# main.net
KiCad netlist of a schematic drawn in Altium Designer
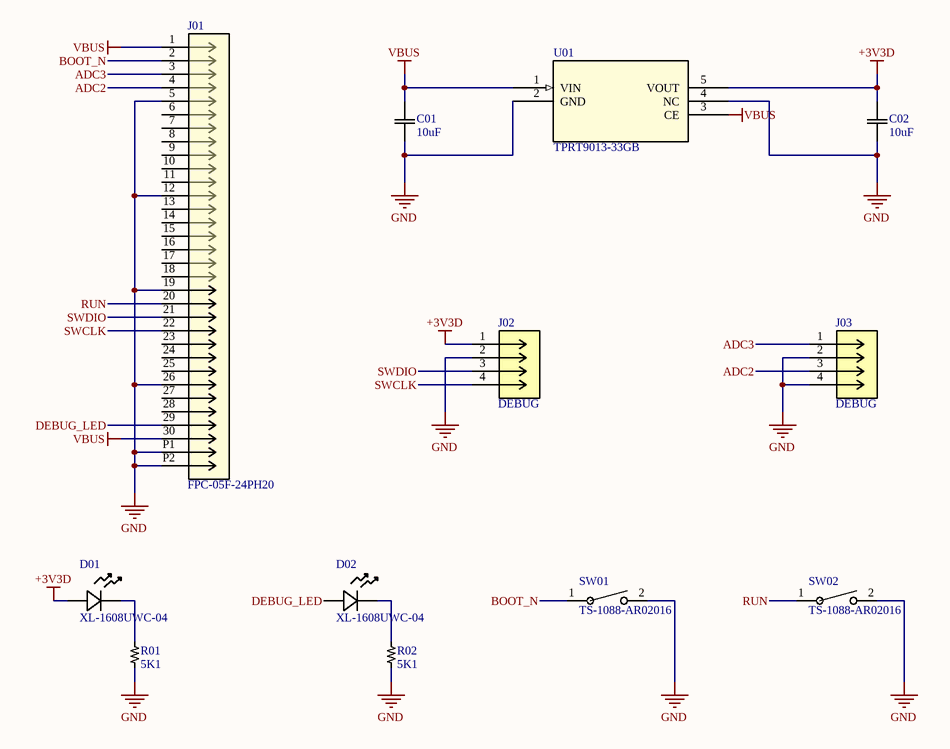
[diagram p0: main.SchDoc]

(export (version "E")
  (design (tool "Eeschema 10.0.6"))
  (components
    (comp (ref "C01")
      (value "10uF")
      (footprint "CAPC10555_55N_KEM")
      (description "SMD Comm X7R, Ceramic, SMD, MLCC, Temperature Stable, 0402")
      (fields
        (field (name "MANUFACTURER_PART_NUMBER") "C0402C104K4RACTU")
        (field (name "COPYRIGHT") "Copyright (C) 2025 Ultra Librarian. All rights reserved.")
      )
      (libsource (lib "SplitHE_Int") (part "C0402"))
    )
    (comp (ref "C02")
      (value "10uF")
      (footprint "CAPC10555_55N_KEM")
      (description "SMD Comm X7R, Ceramic, SMD, MLCC, Temperature Stable, 0402")
      (fields
        (field (name "MANUFACTURER_PART_NUMBER") "C0402C104K4RACTU")
        (field (name "COPYRIGHT") "Copyright (C) 2025 Ultra Librarian. All rights reserved.")
      )
      (libsource (lib "SplitHE_Int") (part "C0402"))
    )
    (comp (ref "D01")
      (value "XL-1608UWC-04")
      (footprint "LED_XL-1608_XLG")
      (description "No Description Available")
      (fields (field (name "COPYRIGHT") "Copyright (C) 2025 Ultra Librarian. All rights reserved."))
      (libsource (lib "SplitHE_Int") (part "XL-1608UWC-04"))
    )
    (comp (ref "D02")
      (value "XL-1608UWC-04")
      (footprint "LED_XL-1608_XLG")
      (description "No Description Available")
      (fields (field (name "COPYRIGHT") "Copyright (C) 2025 Ultra Librarian. All rights reserved."))
      (libsource (lib "SplitHE_Int") (part "XL-1608UWC-04"))
    )
    (comp (ref "J01")
      (value "FPC-05F-24PH20")
      (footprint "FPC-05F-30PH20")
      (description "32 Pin 0.5 Pitch FPC connector")
      (libsource (lib "SplitHE_COPY_073026") (part "FPC-05F-32PH20"))
    )
    (comp (ref "J02")
      (value "DEBUG")
      (footprint "SW_Debugger_4P")
      (description "Back up plan for debugging")
      (libsource (lib "SplitHE_Int") (part "DEBUG_4"))
    )
    (comp (ref "J03")
      (value "DEBUG")
      (footprint "SW_Debugger_4P")
      (description "Back up plan for debugging")
      (libsource (lib "SplitHE_Int") (part "DEBUG_4"))
    )
    (comp (ref "R01")
      (value "5K1")
      (footprint "RES0402_CPF_TYCO_TYC")
      (description "CPF 0402 RL")
      (fields
        (field (name "MANUFACTURER_PART_NUMBER") "CPF0402B33RE1")
        (field (name "COPYRIGHT") "Copyright (C) 2025 Ultra Librarian. All rights reserved.")
      )
      (libsource (lib "SplitHE_Int") (part "R0402"))
    )
    (comp (ref "R02")
      (value "5K1")
      (footprint "RES0402_CPF_TYCO_TYC")
      (description "CPF 0402 RL")
      (fields
        (field (name "MANUFACTURER_PART_NUMBER") "CPF0402B33RE1")
        (field (name "COPYRIGHT") "Copyright (C) 2025 Ultra Librarian. All rights reserved.")
      )
      (libsource (lib "SplitHE_Int") (part "R0402"))
    )
    (comp (ref "SW01")
      (value "TS-1088-AR02016")
      (footprint "SW_TS-1088_XNP")
      (description "Description")
      (fields (field (name "COPYRIGHT") "Copyright (C) 2026 Ultra Librarian. All rights reserved."))
      (libsource (lib "SplitHE_Int") (part "TS-1088-AR02016"))
    )
    (comp (ref "SW02")
      (value "TS-1088-AR02016")
      (footprint "SW_TS-1088_XNP")
      (description "Description")
      (fields (field (name "COPYRIGHT") "Copyright (C) 2026 Ultra Librarian. All rights reserved."))
      (libsource (lib "SplitHE_Int") (part "TS-1088-AR02016"))
    )
    (comp (ref "U01")
      (value "TPRT9013-33GB")
      (footprint "SOT23-5_TCP")
      (description "No Description Available")
      (fields (field (name "COPYRIGHT") "Copyright (C) 2025 Ultra Librarian. All rights reserved."))
      (libsource (lib "SplitHE_Int") (part "TPRT9013-33GB"))
    )
  )
  (nets
    (net (code "1") (name "+3V3D") (class "Default")
      (node (ref "C02") (pin "2") (pinfunction "2_2") (pintype "passive"))
      (node (ref "D01") (pin "2") (pinfunction "ANODE_2") (pintype "passive"))
      (node (ref "J02") (pin "1") (pinfunction "2_1") (pintype "passive"))
      (node (ref "U01") (pin "5") (pinfunction "VOUT_5") (pintype "power_in"))
    )
    (net (code "2") (name "/ADC2") (class "Default")
      (node (ref "J01") (pin "4") (pinfunction "4_4") (pintype "passive"))
      (node (ref "J03") (pin "3") (pinfunction "3_3") (pintype "passive"))
    )
    (net (code "3") (name "/ADC3") (class "Default")
      (node (ref "J01") (pin "3") (pinfunction "3_3") (pintype "passive"))
      (node (ref "J03") (pin "1") (pinfunction "2_1") (pintype "passive"))
    )
    (net (code "4") (name "/BOOT_N") (class "Default")
      (node (ref "J01") (pin "2") (pinfunction "2_2") (pintype "passive"))
      (node (ref "SW01") (pin "1") (pinfunction "1_1") (pintype "passive"))
    )
    (net (code "5") (name "/DEBUG_LED") (class "Default")
      (node (ref "D02") (pin "2") (pinfunction "ANODE_2") (pintype "passive"))
      (node (ref "J01") (pin "29") (pinfunction "29_29") (pintype "passive"))
    )
    (net (code "6") (name "/RUN") (class "Default")
      (node (ref "J01") (pin "20") (pinfunction "20_20") (pintype "passive"))
      (node (ref "SW02") (pin "1") (pinfunction "1_1") (pintype "passive"))
    )
    (net (code "7") (name "/SWCLK") (class "Default")
      (node (ref "J01") (pin "22") (pinfunction "22_22") (pintype "passive"))
      (node (ref "J02") (pin "4") (pinfunction "4_4") (pintype "passive"))
    )
    (net (code "8") (name "/SWDIO") (class "Default")
      (node (ref "J01") (pin "21") (pinfunction "21_21") (pintype "passive"))
      (node (ref "J02") (pin "3") (pinfunction "3_3") (pintype "passive"))
    )
    (net (code "9") (name "GND") (class "Default")
      (node (ref "C01") (pin "1") (pinfunction "1_1") (pintype "passive"))
      (node (ref "C02") (pin "1") (pinfunction "1_1") (pintype "passive"))
      (node (ref "J01") (pin "12") (pinfunction "12_12") (pintype "passive"))
      (node (ref "J01") (pin "19") (pinfunction "19_19") (pintype "passive"))
      (node (ref "J01") (pin "26") (pinfunction "26_26") (pintype "passive"))
      (node (ref "J01") (pin "5") (pinfunction "5_5") (pintype "passive"))
      (node (ref "J01") (pin "P1") (pinfunction "P1_P1") (pintype "passive"))
      (node (ref "J01") (pin "P2") (pinfunction "P2_P2") (pintype "passive"))
      (node (ref "J02") (pin "2") (pinfunction "2_2") (pintype "passive"))
      (node (ref "J03") (pin "2") (pinfunction "2_2") (pintype "passive"))
      (node (ref "J03") (pin "4") (pinfunction "4_4") (pintype "passive"))
      (node (ref "R01") (pin "2") (pinfunction "2_2") (pintype "passive"))
      (node (ref "R02") (pin "2") (pinfunction "2_2") (pintype "passive"))
      (node (ref "SW01") (pin "2") (pinfunction "2_2") (pintype "passive"))
      (node (ref "SW02") (pin "2") (pinfunction "2_2") (pintype "passive"))
      (node (ref "U01") (pin "2") (pinfunction "GND_2") (pintype "power_in"))
      (node (ref "U01") (pin "4") (pinfunction "NC_4") (pintype "passive"))
    )
    (net (code "10") (name "Net-(D01-CATHODE)") (class "Default")
      (node (ref "D01") (pin "1") (pinfunction "CATHODE_1") (pintype "passive"))
      (node (ref "R01") (pin "1") (pinfunction "1_1") (pintype "passive"))
    )
    (net (code "11") (name "Net-(D02-CATHODE)") (class "Default")
      (node (ref "D02") (pin "1") (pinfunction "CATHODE_1") (pintype "passive"))
      (node (ref "R02") (pin "1") (pinfunction "1_1") (pintype "passive"))
    )
    (net (code "12") (name "VBUS") (class "Default")
      (node (ref "C01") (pin "2") (pinfunction "2_2") (pintype "passive"))
      (node (ref "J01") (pin "1") (pinfunction "1_1") (pintype "passive"))
      (node (ref "J01") (pin "30") (pinfunction "30_30") (pintype "passive"))
      (node (ref "U01") (pin "1") (pinfunction "VIN_1") (pintype "input"))
      (node (ref "U01") (pin "3") (pinfunction "CE_3") (pintype "passive"))
    )
    (net (code "13") (name "unconnected-(J01-Pad6)") (class "Default")
      (node (ref "J01") (pin "6") (pinfunction "6_6") (pintype "passive"))
    )
    (net (code "14") (name "unconnected-(J01-Pad7)") (class "Default")
      (node (ref "J01") (pin "7") (pinfunction "7_7") (pintype "passive"))
    )
    (net (code "15") (name "unconnected-(J01-Pad8)") (class "Default")
      (node (ref "J01") (pin "8") (pinfunction "8_8") (pintype "passive"))
    )
    (net (code "16") (name "unconnected-(J01-Pad9)") (class "Default")
      (node (ref "J01") (pin "9") (pinfunction "9_9") (pintype "passive"))
    )
    (net (code "17") (name "unconnected-(J01-Pad10)") (class "Default")
      (node (ref "J01") (pin "10") (pinfunction "10_10") (pintype "passive"))
    )
    (net (code "18") (name "unconnected-(J01-Pad11)") (class "Default")
      (node (ref "J01") (pin "11") (pinfunction "11_11") (pintype "passive"))
    )
    (net (code "19") (name "unconnected-(J01-Pad13)") (class "Default")
      (node (ref "J01") (pin "13") (pinfunction "13_13") (pintype "passive"))
    )
    (net (code "20") (name "unconnected-(J01-Pad14)") (class "Default")
      (node (ref "J01") (pin "14") (pinfunction "14_14") (pintype "passive"))
    )
    (net (code "21") (name "unconnected-(J01-Pad15)") (class "Default")
      (node (ref "J01") (pin "15") (pinfunction "15_15") (pintype "passive"))
    )
    (net (code "22") (name "unconnected-(J01-Pad16)") (class "Default")
      (node (ref "J01") (pin "16") (pinfunction "16_16") (pintype "passive"))
    )
    (net (code "23") (name "unconnected-(J01-Pad17)") (class "Default")
      (node (ref "J01") (pin "17") (pinfunction "17_17") (pintype "passive"))
    )
    (net (code "24") (name "unconnected-(J01-Pad18)") (class "Default")
      (node (ref "J01") (pin "18") (pinfunction "18_18") (pintype "passive"))
    )
    (net (code "25") (name "unconnected-(J01-Pad23)") (class "Default")
      (node (ref "J01") (pin "23") (pinfunction "23_23") (pintype "passive"))
    )
    (net (code "26") (name "unconnected-(J01-Pad24)") (class "Default")
      (node (ref "J01") (pin "24") (pinfunction "24_24") (pintype "passive"))
    )
    (net (code "27") (name "unconnected-(J01-Pad25)") (class "Default")
      (node (ref "J01") (pin "25") (pinfunction "25_25") (pintype "passive"))
    )
    (net (code "28") (name "unconnected-(J01-Pad27)") (class "Default")
      (node (ref "J01") (pin "27") (pinfunction "27_27") (pintype "passive"))
    )
    (net (code "29") (name "unconnected-(J01-Pad28)") (class "Default")
      (node (ref "J01") (pin "28") (pinfunction "28_28") (pintype "passive"))
    )
  )
)
